# imu_spi.net
KiCad netlist of a schematic drawn in EAGLE
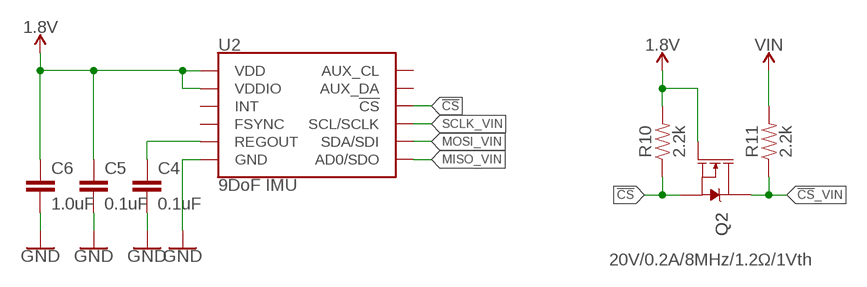
[diagram p0: schematic, sheet 1]

(export (version "E")
  (design (tool "Eeschema 10.0.6"))
  (components
    (comp (ref "C4")
      (value "0.1uF")
      (footprint "eagle-import:C0402")
      (libsource (lib "eagle-import") (part "C-EUC0402"))
    )
    (comp (ref "C5")
      (value "0.1uF")
      (footprint "eagle-import:C0402")
      (libsource (lib "eagle-import") (part "C-EUC0402"))
    )
    (comp (ref "C6")
      (value "1.0uF")
      (footprint "eagle-import:C0402")
      (libsource (lib "eagle-import") (part "C-EUC0402"))
    )
    (comp (ref "Q2")
      (value "20V/0.2A/8MHz/1.2Ω/1Vth")
      (footprint "eagle-import:SOT-416FL")
      (libsource (lib "eagle-import") (part "MOSFET-NCH-RE1C002UN"))
    )
    (comp (ref "R10")
      (value "2.2k")
      (footprint "eagle-import:0402-TIGHT")
      (libsource (lib "eagle-import") (part "2.2KOHM-0402T-1/16W-1%"))
    )
    (comp (ref "R11")
      (value "2.2k")
      (footprint "eagle-import:0402-TIGHT")
      (libsource (lib "eagle-import") (part "2.2KOHM-0402T-1/16W-1%"))
    )
    (comp (ref "U2")
      (value "9DoF IMU")
      (footprint "eagle-import:QFN24-3X3")
      (libsource (lib "eagle-import") (part "ICM-20948"))
    )
  )
  (nets
    (net (code "1") (name "/~{CS}") (class "Default")
      (node (ref "Q2") (pin "2") (pinfunction "S_2") (pintype "bidirectional"))
      (node (ref "R10") (pin "1") (pinfunction "1_1") (pintype "passive"))
      (node (ref "U2") (pin "22") (pinfunction "~{CS}_22") (pintype "bidirectional"))
    )
    (net (code "2") (name "/~{CS}_VIN") (class "Default")
      (node (ref "Q2") (pin "3") (pinfunction "D_3") (pintype "bidirectional"))
      (node (ref "R11") (pin "1") (pinfunction "1_1") (pintype "passive"))
    )
    (net (code "3") (name "1.8V") (class "Default")
      (node (ref "C5") (pin "1") (pinfunction "1_1") (pintype "passive"))
      (node (ref "C6") (pin "1") (pinfunction "1_1") (pintype "passive"))
      (node (ref "Q2") (pin "1") (pinfunction "G_1") (pintype "bidirectional"))
      (node (ref "R10") (pin "2") (pinfunction "2_2") (pintype "passive"))
      (node (ref "U2") (pin "13") (pinfunction "VDD_13") (pintype "bidirectional"))
      (node (ref "U2") (pin "8") (pinfunction "VDDIO_8") (pintype "bidirectional"))
    )
    (net (code "4") (name "GND") (class "Default")
      (node (ref "C4") (pin "2") (pinfunction "2_2") (pintype "passive"))
      (node (ref "C5") (pin "2") (pinfunction "2_2") (pintype "passive"))
      (node (ref "C6") (pin "2") (pinfunction "2_2") (pintype "passive"))
      (node (ref "U2") (pin "18") (pinfunction "GND_18") (pintype "bidirectional"))
      (node (ref "U2") (pin "20") (pinfunction "GND_20") (pintype "bidirectional"))
    )
    (net (code "5") (name "MISO_VIN") (class "Default")
      (node (ref "U2") (pin "9") (pinfunction "AD0/SDO_9") (pintype "bidirectional"))
    )
    (net (code "6") (name "MOSI_VIN") (class "Default")
      (node (ref "U2") (pin "24") (pinfunction "SDA/SDI_24") (pintype "bidirectional"))
    )
    (net (code "7") (name "Net-(U2-REGOUT)") (class "Default")
      (node (ref "C4") (pin "1") (pinfunction "1_1") (pintype "passive"))
      (node (ref "U2") (pin "10") (pinfunction "REGOUT_10") (pintype "bidirectional"))
    )
    (net (code "8") (name "SCLK_VIN") (class "Default")
      (node (ref "U2") (pin "23") (pinfunction "SCL/SCLK_23") (pintype "bidirectional"))
    )
    (net (code "9") (name "VIN") (class "Default")
      (node (ref "R11") (pin "2") (pinfunction "2_2") (pintype "passive"))
    )
    (net (code "10") (name "unconnected-(U2-AUX_CL-Pad7)") (class "Default")
      (node (ref "U2") (pin "7") (pinfunction "AUX_CL_7") (pintype "bidirectional"))
    )
    (net (code "11") (name "unconnected-(U2-AUX_DA-Pad21)") (class "Default")
      (node (ref "U2") (pin "21") (pinfunction "AUX_DA_21") (pintype "bidirectional"))
    )
    (net (code "12") (name "unconnected-(U2-FSYNC-Pad11)") (class "Default")
      (node (ref "U2") (pin "11") (pinfunction "FSYNC_11") (pintype "bidirectional"))
    )
    (net (code "13") (name "unconnected-(U2-INT-Pad12)") (class "Default")
      (node (ref "U2") (pin "12") (pinfunction "INT_12") (pintype "bidirectional"))
    )
  )
)
